# Sensor_Schematic.net
KiCad netlist of a schematic drawn in Altium Designer
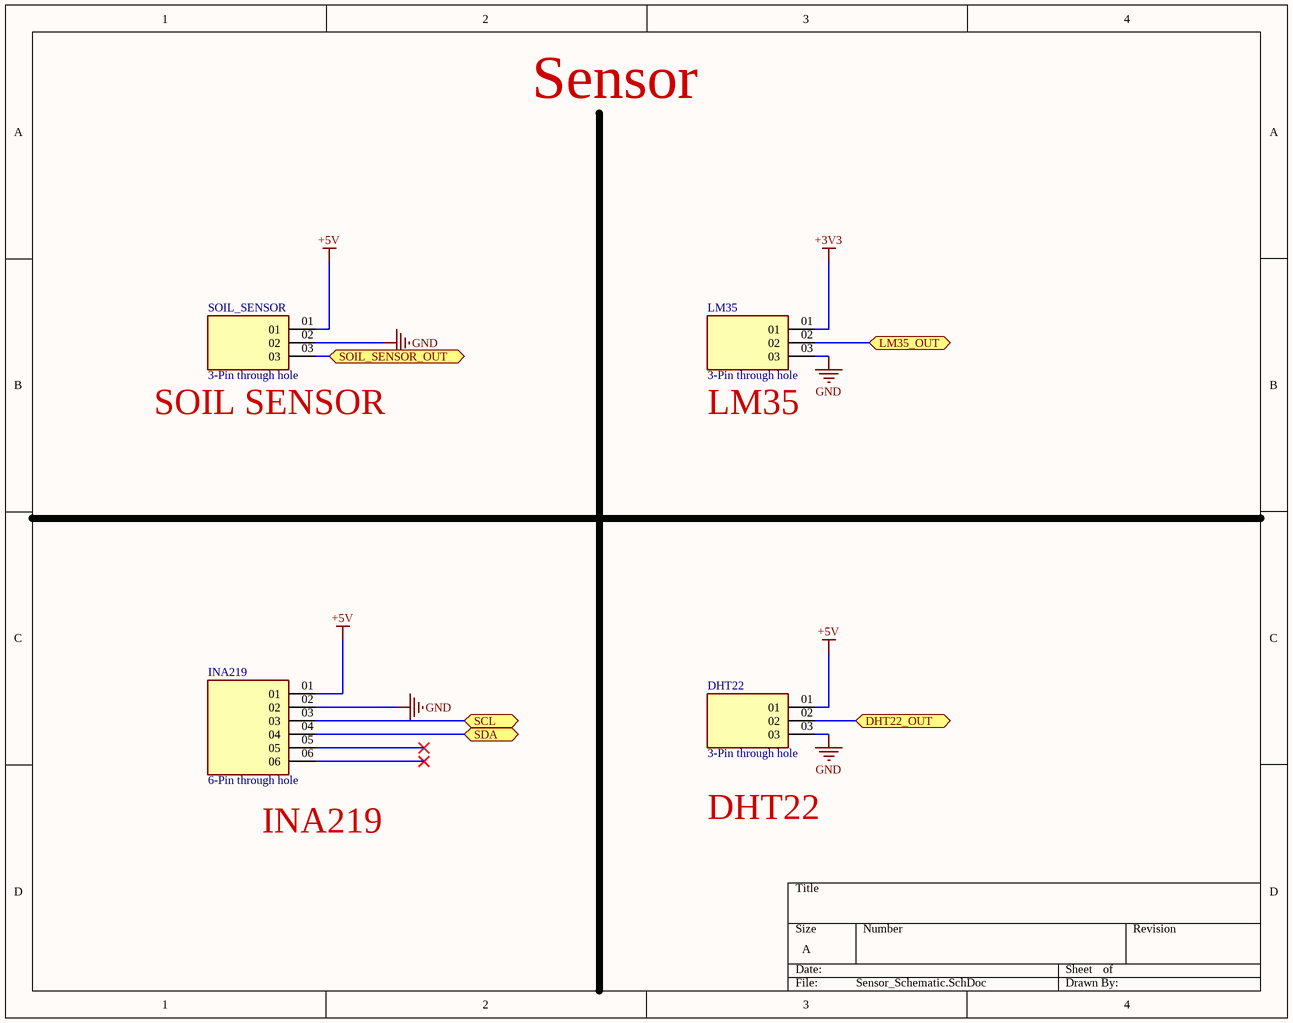
[diagram p0: Sensor_Schematic.SchDoc]

(export (version "E")
  (design (tool "Eeschema 10.0.6"))
  (components
    (comp (ref "DHT22")
      (value "3-Pin through hole")
      (footprint "SAMTEC_MTSW-101-08-G-T-240")
      (fields (field (name "MP") "altium_native_batch"))
      (libsource (lib "ESP_LoRa_schematic_lib") (part "3-Pin through hole"))
    )
    (comp (ref "INA219")
      (value "6-Pin through hole")
      (footprint "SAMTEC_MTSW-106-22-G-S-235 - duplicate1")
      (fields (field (name "MP") "MTSW-106-22-G-S-235"))
      (libsource (lib "ESP_LoRa_schematic_lib") (part "6-Pin through hole"))
    )
    (comp (ref "LM35")
      (value "3-Pin through hole")
      (footprint "SAMTEC_MTSW-101-08-G-T-240")
      (fields (field (name "MP") "altium_native_batch"))
      (libsource (lib "ESP_LoRa_schematic_lib") (part "3-Pin through hole"))
    )
    (comp (ref "SOIL_SENSOR")
      (value "3-Pin through hole")
      (footprint "SAMTEC_MTSW-101-08-G-T-240")
      (fields (field (name "MP") "altium_native_batch"))
      (libsource (lib "ESP_LoRa_schematic_lib") (part "3-Pin through hole"))
    )
  )
  (nets
    (net (code "1") (name "+3V3") (class "Default")
      (node (ref "LM35") (pin "01") (pinfunction "01_01") (pintype "passive"))
    )
    (net (code "2") (name "+5V") (class "Default")
      (node (ref "DHT22") (pin "01") (pinfunction "01_01") (pintype "passive"))
      (node (ref "INA219") (pin "01") (pinfunction "01_01") (pintype "passive"))
      (node (ref "SOIL_SENSOR") (pin "01") (pinfunction "01_01") (pintype "passive"))
    )
    (net (code "3") (name "/DHT22_OUT") (class "Default")
      (node (ref "DHT22") (pin "02") (pinfunction "02_02") (pintype "passive"))
    )
    (net (code "4") (name "/LM35_OUT") (class "Default")
      (node (ref "LM35") (pin "02") (pinfunction "02_02") (pintype "passive"))
    )
    (net (code "5") (name "/SCL") (class "Default")
      (node (ref "INA219") (pin "03") (pinfunction "03_03") (pintype "passive"))
    )
    (net (code "6") (name "/SDA") (class "Default")
      (node (ref "INA219") (pin "04") (pinfunction "04_04") (pintype "passive"))
    )
    (net (code "7") (name "/SOIL_SENSOR_OUT") (class "Default")
      (node (ref "SOIL_SENSOR") (pin "03") (pinfunction "03_03") (pintype "passive"))
    )
    (net (code "8") (name "GND") (class "Default")
      (node (ref "DHT22") (pin "03") (pinfunction "03_03") (pintype "passive"))
      (node (ref "INA219") (pin "02") (pinfunction "02_02") (pintype "passive"))
      (node (ref "LM35") (pin "03") (pinfunction "03_03") (pintype "passive"))
      (node (ref "SOIL_SENSOR") (pin "02") (pinfunction "02_02") (pintype "passive"))
    )
    (net (code "9") (name "unconnected-(INA219-Pad05)") (class "Default")
      (node (ref "INA219") (pin "05") (pinfunction "05_05") (pintype "passive+no_connect"))
    )
    (net (code "10") (name "unconnected-(INA219-Pad06)") (class "Default")
      (node (ref "INA219") (pin "06") (pinfunction "06_06") (pintype "passive+no_connect"))
    )
  )
)
